# Top_Level.net
KiCad netlist of a schematic drawn in Altium Designer
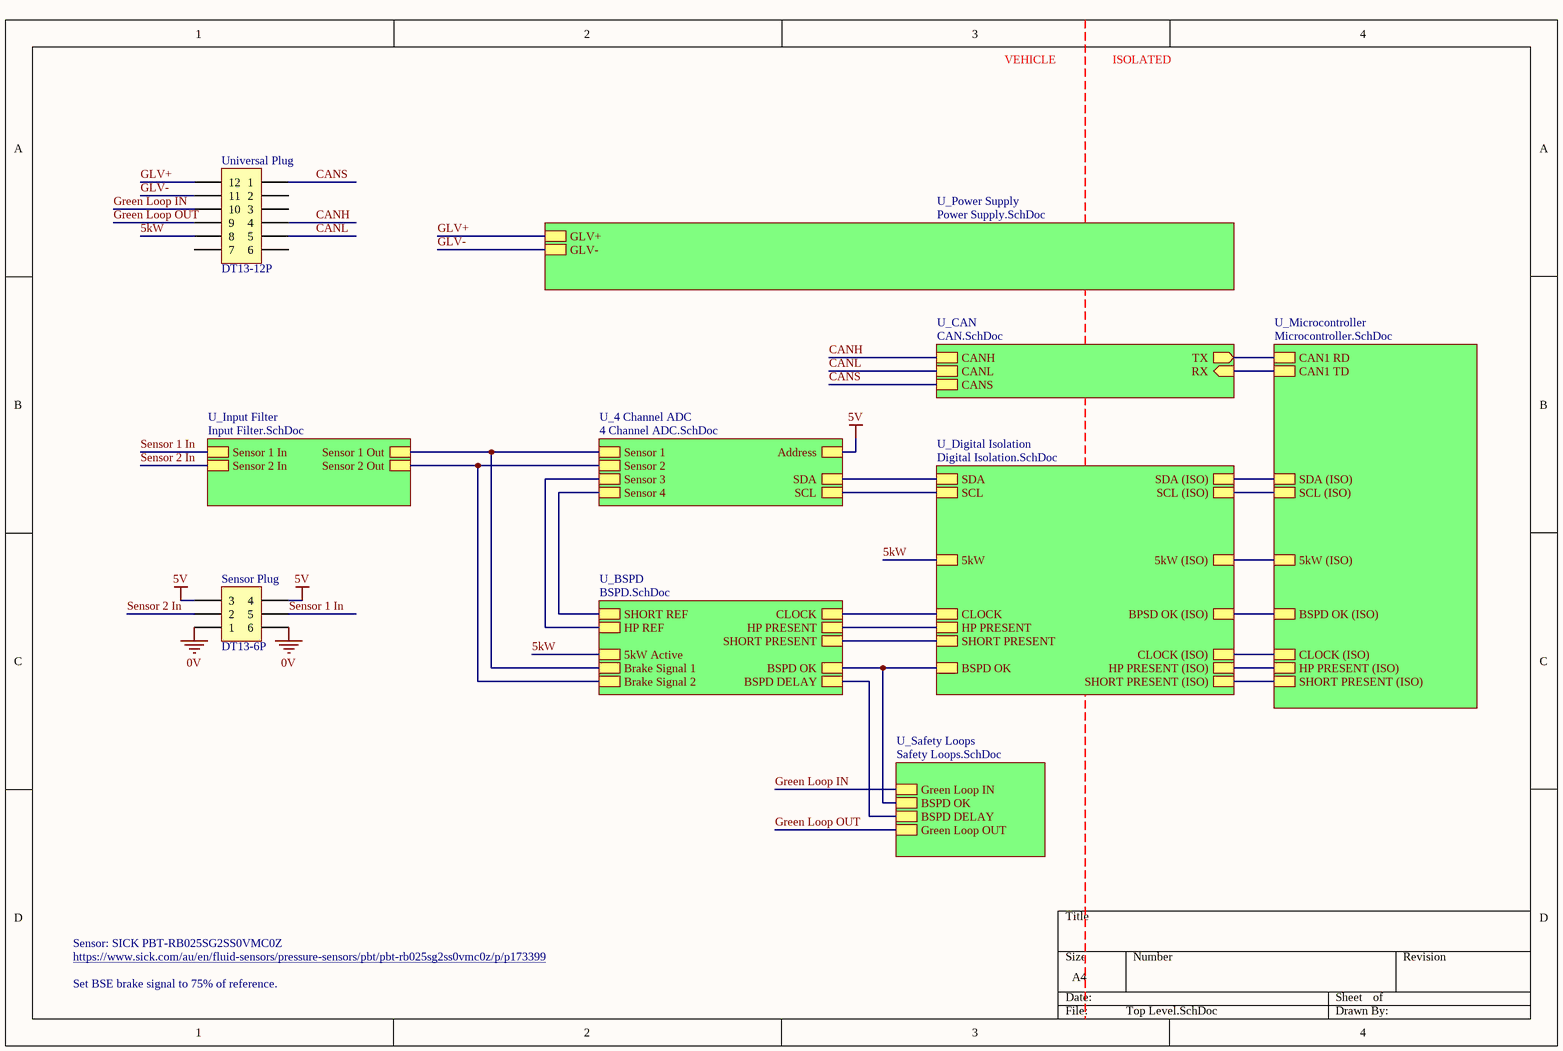
[diagram p0: Top Level.SchDoc]

(export (version "E")
  (design (tool "Eeschema 10.0.6"))
  (components
    (comp (ref "Sensor Plug")
      (value "DT13-6P")
      (footprint "DT13-6P")
      (fields (field (name "DIGIKEY PART NUMBER") "1734-1025-ND") (field (name "CONTACT") "Copper Alloy"))
      (libsource (lib "ts_20-standard-connectors") (part "DT13-6P"))
    )
    (comp (ref "Universal Plug")
      (value "DT13-12P")
      (footprint "DT13-12P")
      (fields (field (name "DIGIKEY PART NUMBER") "1734-1451-ND") (field (name "CONTACT") "Nickel"))
      (libsource (lib "ts_20-standard-connectors") (part "DT13-12P"))
    )
  )
  (nets
    (net (code "1") (name "/5kW") (class "Default")
      (node (ref "Universal Plug") (pin "8") (pinfunction "8_8") (pintype "passive"))
    )
    (net (code "9") (name "/CANH") (class "Default")
      (node (ref "Universal Plug") (pin "4") (pinfunction "4_4") (pintype "power_in"))
    )
    (net (code "10") (name "/CANL") (class "Default")
      (node (ref "Universal Plug") (pin "5") (pinfunction "5_5") (pintype "power_in"))
    )
    (net (code "11") (name "/CANS") (class "Default")
      (node (ref "Universal Plug") (pin "1") (pinfunction "1_1") (pintype "power_in"))
    )
    (net (code "14") (name "/GLV+") (class "Default")
      (node (ref "Universal Plug") (pin "12") (pinfunction "12_12") (pintype "passive"))
    )
    (net (code "15") (name "/GLV-") (class "Default")
      (node (ref "Universal Plug") (pin "11") (pinfunction "11_11") (pintype "passive"))
    )
    (net (code "16") (name "/Green Loop IN") (class "Default")
      (node (ref "Universal Plug") (pin "10") (pinfunction "10_10") (pintype "passive"))
    )
    (net (code "17") (name "/Green Loop OUT") (class "Default")
      (node (ref "Universal Plug") (pin "9") (pinfunction "9_9") (pintype "passive"))
    )
    (net (code "28") (name "/Sensor 1 In") (class "Default")
      (node (ref "Sensor Plug") (pin "5") (pinfunction "5_5") (pintype "passive"))
    )
    (net (code "29") (name "/Sensor 2 In") (class "Default")
      (node (ref "Sensor Plug") (pin "2") (pinfunction "2_2") (pintype "power_in"))
    )
    (net (code "31") (name "0V") (class "Default")
      (node (ref "Sensor Plug") (pin "1") (pinfunction "1_1") (pintype "power_in"))
      (node (ref "Sensor Plug") (pin "6") (pinfunction "6_6") (pintype "passive"))
    )
    (net (code "32") (name "5V") (class "Default")
      (node (ref "Sensor Plug") (pin "3") (pinfunction "3_3") (pintype "power_in"))
      (node (ref "Sensor Plug") (pin "4") (pinfunction "4_4") (pintype "passive"))
    )
    (net (code "33") (name "unconnected-(Universal Plug-Pad2)") (class "Default")
      (node (ref "Universal Plug") (pin "2") (pinfunction "2_2") (pintype "power_in"))
    )
    (net (code "34") (name "unconnected-(Universal Plug-Pad3)") (class "Default")
      (node (ref "Universal Plug") (pin "3") (pinfunction "3_3") (pintype "power_in"))
    )
    (net (code "35") (name "unconnected-(Universal Plug-Pad6)") (class "Default")
      (node (ref "Universal Plug") (pin "6") (pinfunction "6_6") (pintype "power_in"))
    )
    (net (code "36") (name "unconnected-(Universal Plug-Pad7)") (class "Default")
      (node (ref "Universal Plug") (pin "7") (pinfunction "7_7") (pintype "passive"))
    )
  )
)
